# IO4-LED-Strip-Driver.net
KiCad netlist of a schematic drawn in EAGLE
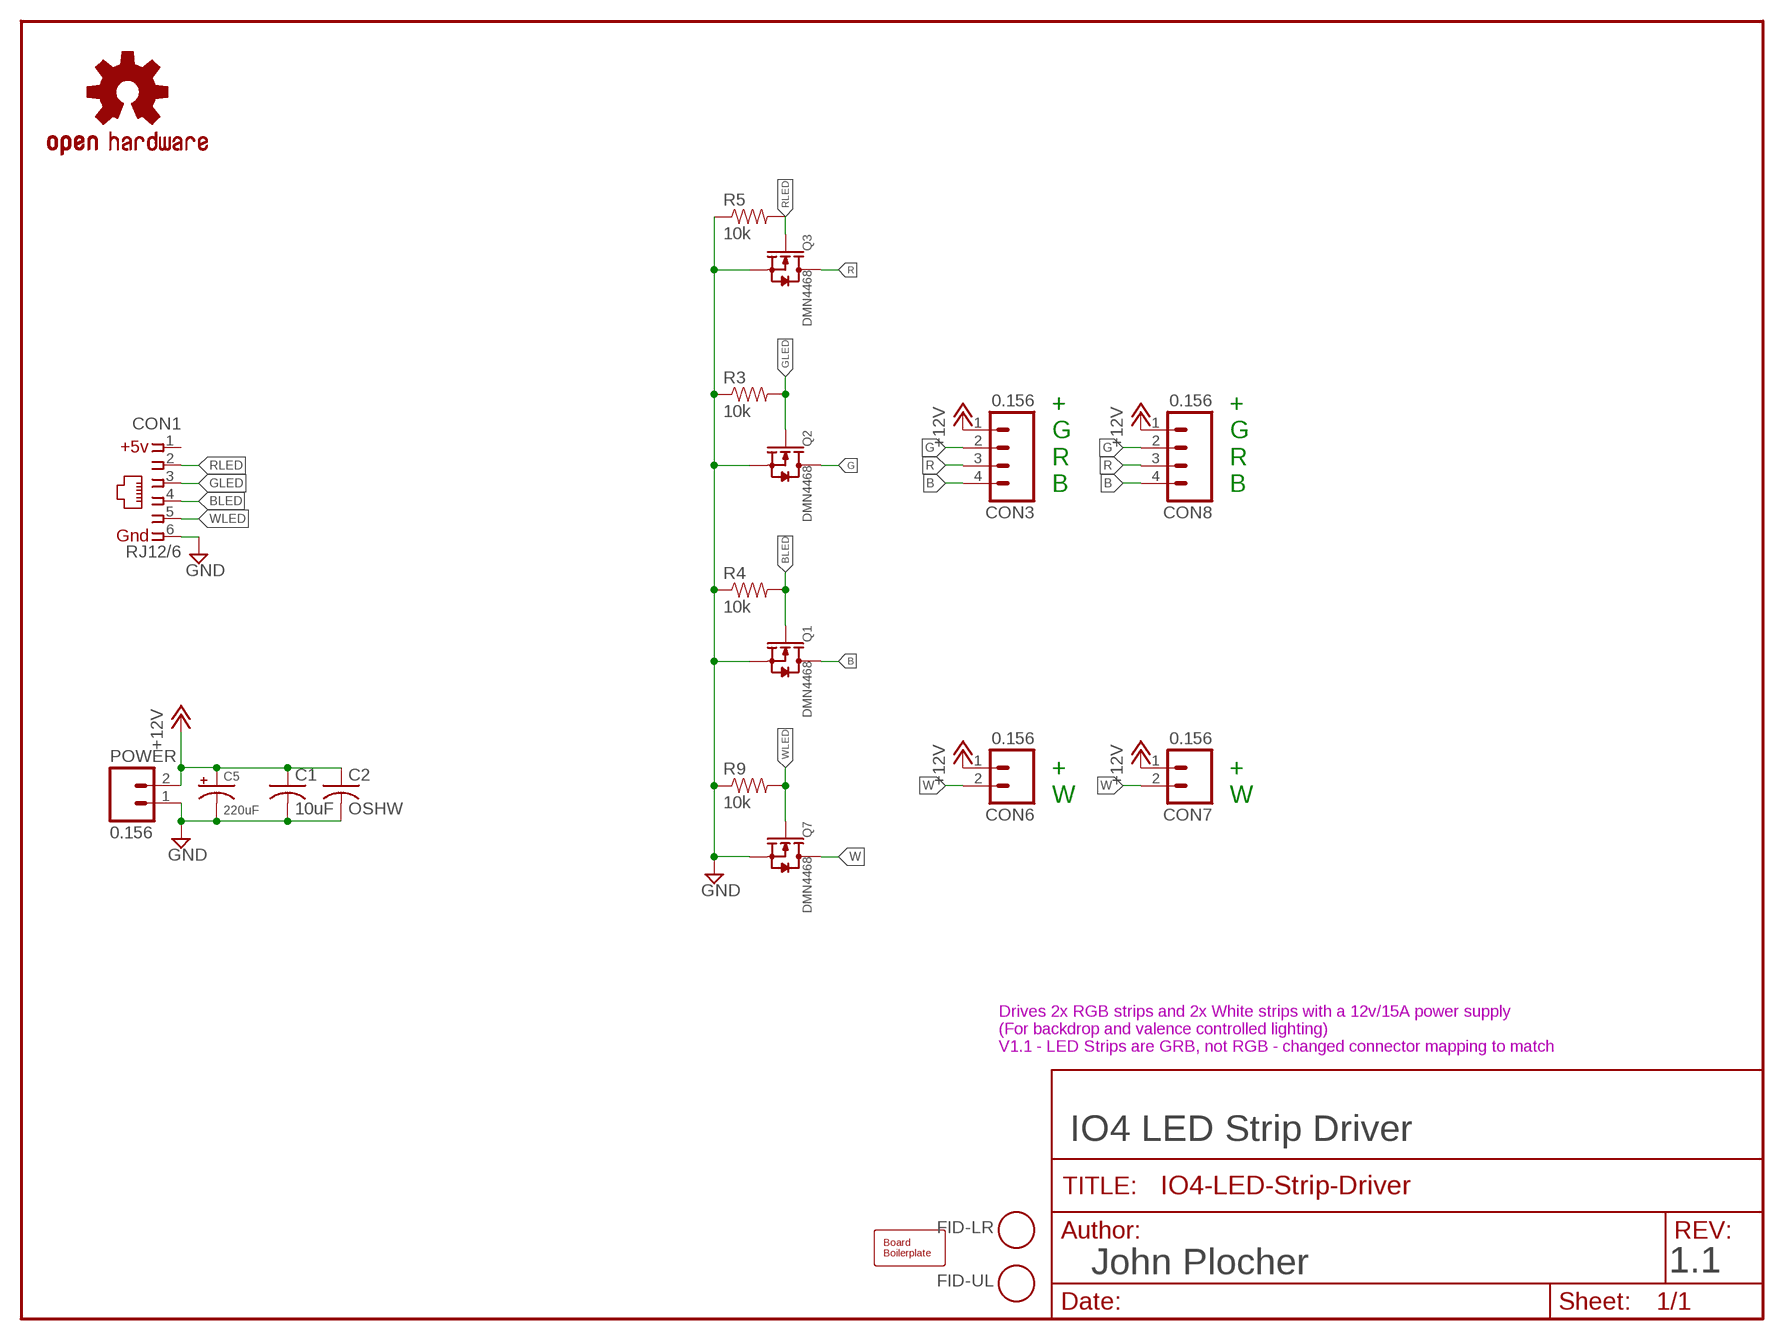
[diagram p0: schematic, sheet 1]

(export (version "E")
  (design (tool "Eeschema 10.0.6"))
  (components
    (comp (ref "BOARD1")
      (value "BOARD")
      (footprint "eagle-import:BOARD-DINRAIL-3.17INX10CM")
      (libsource (lib "eagle-import") (part "BOARD80X100"))
    )
    (comp (ref "C1")
      (value "10uF")
      (footprint "eagle-import:0603-CAP")
      (libsource (lib "eagle-import") (part "CAP0603"))
    )
    (comp (ref "C2")
      (value "OSHW")
      (footprint "eagle-import:0603-CAP")
      (libsource (lib "eagle-import") (part "CAP0603"))
    )
    (comp (ref "C5")
      (value "220uF")
      (footprint "eagle-import:0810-CAP")
      (libsource (lib "eagle-import") (part "CAP-POL0810"))
    )
    (comp (ref "CON1")
      (value "RJ12/6")
      (footprint "eagle-import:RJ25-INVERTED")
      (libsource (lib "eagle-import") (part "CONNECTOR-IO4INV"))
    )
    (comp (ref "CON3")
      (value "0.156")
      (footprint "eagle-import:MSTBA4")
      (libsource (lib "eagle-import") (part "CONNECTOR-M045.08"))
    )
    (comp (ref "CON6")
      (value "0.156")
      (footprint "eagle-import:MSTBA2")
      (libsource (lib "eagle-import") (part "CONNECTOR-M02MSTBA2"))
    )
    (comp (ref "CON7")
      (value "0.156")
      (footprint "eagle-import:MSTBA2")
      (libsource (lib "eagle-import") (part "CONNECTOR-M02MSTBA2"))
    )
    (comp (ref "CON8")
      (value "0.156")
      (footprint "eagle-import:MSTBA4")
      (libsource (lib "eagle-import") (part "CONNECTOR-M045.08"))
    )
    (comp (ref "FID-LR")
      (value "FIDUCIAL")
      (footprint "eagle-import:FIDUCIAL_1MM")
      (libsource (lib "eagle-import") (part "FIDUCIAL"))
    )
    (comp (ref "FID-UL")
      (value "FIDUCIAL")
      (footprint "eagle-import:FIDUCIAL_1MM")
      (libsource (lib "eagle-import") (part "FIDUCIAL"))
    )
    (comp (ref "OSHW1")
      (value "OSHW")
      (footprint "eagle-import:OSHW-LOGO-L")
      (libsource (lib "eagle-import") (part "OSHW-LOGOL"))
    )
    (comp (ref "POWER")
      (value "0.156")
      (footprint "eagle-import:MSTBA2")
      (libsource (lib "eagle-import") (part "CONNECTOR-M02MSTBA2"))
    )
    (comp (ref "Q1")
      (value "DMN4468")
      (footprint "eagle-import:SO08")
      (libsource (lib "eagle-import") (part "MOSFET-N--?SO8"))
    )
    (comp (ref "Q2")
      (value "DMN4468")
      (footprint "eagle-import:SO08")
      (libsource (lib "eagle-import") (part "MOSFET-N--?SO8"))
    )
    (comp (ref "Q3")
      (value "DMN4468")
      (footprint "eagle-import:SO08")
      (libsource (lib "eagle-import") (part "MOSFET-N--?SO8"))
    )
    (comp (ref "Q7")
      (value "DMN4468")
      (footprint "eagle-import:SO08")
      (libsource (lib "eagle-import") (part "MOSFET-N--?SO8"))
    )
    (comp (ref "R3")
      (value "10k")
      (footprint "eagle-import:0603-RES")
      (libsource (lib "eagle-import") (part "R0603-RES"))
    )
    (comp (ref "R4")
      (value "10k")
      (footprint "eagle-import:0603-RES")
      (libsource (lib "eagle-import") (part "R0603-RES"))
    )
    (comp (ref "R5")
      (value "10k")
      (footprint "eagle-import:0603-RES")
      (libsource (lib "eagle-import") (part "R0603-RES"))
    )
    (comp (ref "R9")
      (value "10k")
      (footprint "eagle-import:0603-RES")
      (libsource (lib "eagle-import") (part "R0603-RES"))
    )
  )
  (nets
    (net (code "1") (name "+12V") (class "Default")
      (node (ref "C1") (pin "1") (pinfunction "1_1") (pintype "passive"))
      (node (ref "C2") (pin "1") (pinfunction "1_1") (pintype "passive"))
      (node (ref "C5") (pin "+") (pinfunction "+_+") (pintype "passive"))
      (node (ref "CON3") (pin "1") (pinfunction "1_1") (pintype "passive"))
      (node (ref "CON6") (pin "1") (pinfunction "A_1") (pintype "passive"))
      (node (ref "CON7") (pin "1") (pinfunction "A_1") (pintype "passive"))
      (node (ref "CON8") (pin "1") (pinfunction "1_1") (pintype "passive"))
      (node (ref "POWER") (pin "2") (pinfunction "B_2") (pintype "passive"))
    )
    (net (code "2") (name "/1") (class "Default")
      (node (ref "CON1") (pin "1") (pinfunction "1_1") (pintype "power_in"))
    )
    (net (code "3") (name "B") (class "Default")
      (node (ref "CON3") (pin "4") (pinfunction "4_4") (pintype "passive"))
      (node (ref "CON8") (pin "4") (pinfunction "4_4") (pintype "passive"))
      (node (ref "Q1") (pin "5") (pinfunction "D_5") (pintype "passive"))
      (node (ref "Q1") (pin "6") (pinfunction "D_6") (pintype "passive"))
      (node (ref "Q1") (pin "7") (pinfunction "D_7") (pintype "passive"))
      (node (ref "Q1") (pin "8") (pinfunction "D_8") (pintype "passive"))
    )
    (net (code "4") (name "BLED") (class "Default")
      (node (ref "CON1") (pin "4") (pinfunction "4_4") (pintype "passive"))
      (node (ref "Q1") (pin "4") (pinfunction "G_4") (pintype "passive"))
      (node (ref "R4") (pin "2") (pinfunction "2_2") (pintype "passive"))
    )
    (net (code "5") (name "G") (class "Default")
      (node (ref "CON3") (pin "2") (pinfunction "2_2") (pintype "passive"))
      (node (ref "CON8") (pin "2") (pinfunction "2_2") (pintype "passive"))
      (node (ref "Q2") (pin "5") (pinfunction "D_5") (pintype "passive"))
      (node (ref "Q2") (pin "6") (pinfunction "D_6") (pintype "passive"))
      (node (ref "Q2") (pin "7") (pinfunction "D_7") (pintype "passive"))
      (node (ref "Q2") (pin "8") (pinfunction "D_8") (pintype "passive"))
    )
    (net (code "6") (name "GLED") (class "Default")
      (node (ref "CON1") (pin "3") (pinfunction "3_3") (pintype "passive"))
      (node (ref "Q2") (pin "4") (pinfunction "G_4") (pintype "passive"))
      (node (ref "R3") (pin "2") (pinfunction "2_2") (pintype "passive"))
    )
    (net (code "7") (name "GND") (class "Default")
      (node (ref "C1") (pin "2") (pinfunction "2_2") (pintype "passive"))
      (node (ref "C2") (pin "2") (pinfunction "2_2") (pintype "passive"))
      (node (ref "C5") (pin "-") (pinfunction "-_-") (pintype "passive"))
      (node (ref "CON1") (pin "6") (pinfunction "6_6") (pintype "power_in"))
      (node (ref "POWER") (pin "1") (pinfunction "A_1") (pintype "passive"))
      (node (ref "Q1") (pin "1") (pinfunction "S_1") (pintype "passive"))
      (node (ref "Q1") (pin "2") (pinfunction "S_2") (pintype "passive"))
      (node (ref "Q1") (pin "3") (pinfunction "S_3") (pintype "passive"))
      (node (ref "Q2") (pin "1") (pinfunction "S_1") (pintype "passive"))
      (node (ref "Q2") (pin "2") (pinfunction "S_2") (pintype "passive"))
      (node (ref "Q2") (pin "3") (pinfunction "S_3") (pintype "passive"))
      (node (ref "Q3") (pin "1") (pinfunction "S_1") (pintype "passive"))
      (node (ref "Q3") (pin "2") (pinfunction "S_2") (pintype "passive"))
      (node (ref "Q3") (pin "3") (pinfunction "S_3") (pintype "passive"))
      (node (ref "Q7") (pin "1") (pinfunction "S_1") (pintype "passive"))
      (node (ref "Q7") (pin "2") (pinfunction "S_2") (pintype "passive"))
      (node (ref "Q7") (pin "3") (pinfunction "S_3") (pintype "passive"))
      (node (ref "R3") (pin "1") (pinfunction "1_1") (pintype "passive"))
      (node (ref "R4") (pin "1") (pinfunction "1_1") (pintype "passive"))
      (node (ref "R5") (pin "1") (pinfunction "1_1") (pintype "passive"))
      (node (ref "R9") (pin "1") (pinfunction "1_1") (pintype "passive"))
    )
    (net (code "8") (name "R") (class "Default")
      (node (ref "CON3") (pin "3") (pinfunction "3_3") (pintype "passive"))
      (node (ref "CON8") (pin "3") (pinfunction "3_3") (pintype "passive"))
      (node (ref "Q3") (pin "5") (pinfunction "D_5") (pintype "passive"))
      (node (ref "Q3") (pin "6") (pinfunction "D_6") (pintype "passive"))
      (node (ref "Q3") (pin "7") (pinfunction "D_7") (pintype "passive"))
      (node (ref "Q3") (pin "8") (pinfunction "D_8") (pintype "passive"))
    )
    (net (code "9") (name "RLED") (class "Default")
      (node (ref "CON1") (pin "2") (pinfunction "2_2") (pintype "passive"))
      (node (ref "Q3") (pin "4") (pinfunction "G_4") (pintype "passive"))
      (node (ref "R5") (pin "2") (pinfunction "2_2") (pintype "passive"))
    )
    (net (code "10") (name "W") (class "Default")
      (node (ref "CON6") (pin "2") (pinfunction "B_2") (pintype "passive"))
      (node (ref "CON7") (pin "2") (pinfunction "B_2") (pintype "passive"))
      (node (ref "Q7") (pin "5") (pinfunction "D_5") (pintype "passive"))
      (node (ref "Q7") (pin "6") (pinfunction "D_6") (pintype "passive"))
      (node (ref "Q7") (pin "7") (pinfunction "D_7") (pintype "passive"))
      (node (ref "Q7") (pin "8") (pinfunction "D_8") (pintype "passive"))
    )
    (net (code "11") (name "WLED") (class "Default")
      (node (ref "CON1") (pin "5") (pinfunction "5_5") (pintype "passive"))
      (node (ref "Q7") (pin "4") (pinfunction "G_4") (pintype "passive"))
      (node (ref "R9") (pin "2") (pinfunction "2_2") (pintype "passive"))
    )
  )
)
